# Serial_IO.net
KiCad netlist of a schematic drawn in Altium Designer
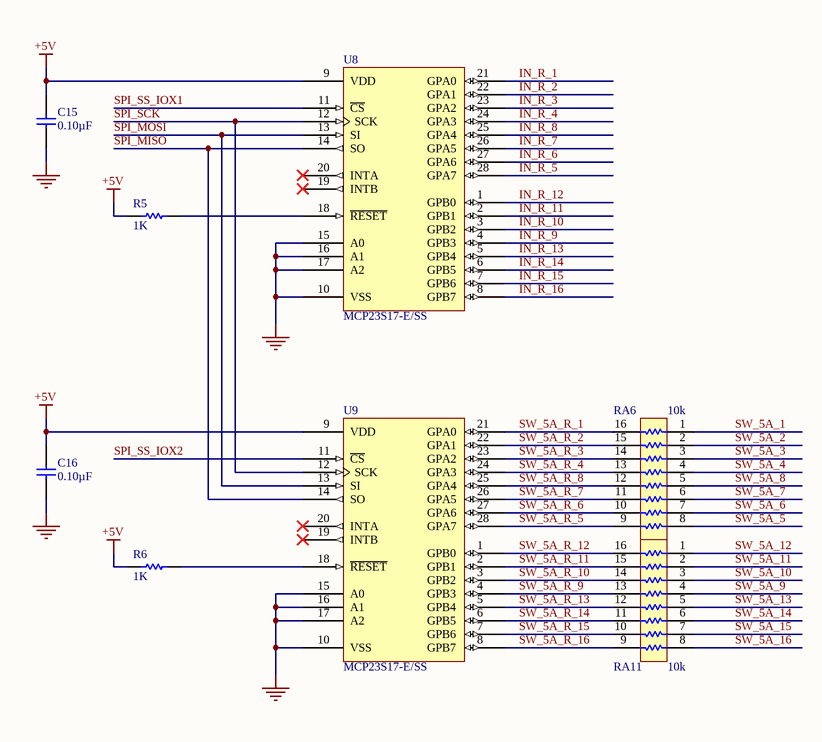
[diagram p0: Serial IO.SchDoc]

(export (version "E")
  (design (tool "Eeschema 10.0.6"))
  (components
    (comp (ref "C15")
      (value "0.10µF")
      (footprint "CAP-0402-M")
      (fields
        (field (name "PART NUMBER") "CC0402KRX7R7BB104")
        (field (name "TOLERANCE") "±10%")
        (field (name "VOLTAGE") "16V")
      )
      (libsource (lib "Capacitors") (part "Capacitor"))
    )
    (comp (ref "C16")
      (value "0.10µF")
      (footprint "CAP-0402-M")
      (fields
        (field (name "PART NUMBER") "CC0402KRX7R7BB104")
        (field (name "TOLERANCE") "±10%")
        (field (name "VOLTAGE") "16V")
      )
      (libsource (lib "Capacitors") (part "Capacitor"))
    )
    (comp (ref "R5")
      (value "1K")
      (footprint "RES-0603-M")
      (fields
        (field (name "PART NUMBER") "RC0603FR-071KL")
        (field (name "TOLERANCE") "1%")
        (field (name "POWER") "1/10 W")
      )
      (libsource (lib "Resistors") (part "Resistor"))
    )
    (comp (ref "R6")
      (value "1K")
      (footprint "RES-0603-M")
      (fields
        (field (name "PART NUMBER") "RC0603FR-071KL")
        (field (name "TOLERANCE") "1%")
        (field (name "POWER") "1/10 W")
      )
      (libsource (lib "Resistors") (part "Resistor"))
    )
    (comp (ref "RA6")
      (value "10k")
      (footprint "CAC-50P379X150-16N")
      (fields (field (name "Comment") "MNR18ERAPJ103"))
      (libsource (lib "PDU-UV17") (part "MNR18ERAPJ103"))
    )
    (comp (ref "RA11")
      (value "10k")
      (footprint "CAC-50P379X150-16N")
      (fields (field (name "Comment") "MNR18ERAPJ103"))
      (libsource (lib "PDU-UV17") (part "MNR18ERAPJ103"))
    )
    (comp (ref "U8")
      (value "MCP23S17-E/SS")
      (footprint "SOP65P780X185-28N")
      (libsource (lib "PDU-UV17") (part "MCP23S17-E/SS"))
    )
    (comp (ref "U9")
      (value "MCP23S17-E/SS")
      (footprint "SOP65P780X185-28N")
      (libsource (lib "PDU-UV17") (part "MCP23S17-E/SS"))
    )
  )
  (nets
    (net (code "1") (name "+5V") (class "Default")
      (node (ref "C15") (pin "2") (pinfunction "2_2") (pintype "passive"))
      (node (ref "C16") (pin "2") (pinfunction "2_2") (pintype "passive"))
      (node (ref "R5") (pin "1") (pinfunction "1_1") (pintype "passive"))
      (node (ref "R6") (pin "1") (pinfunction "1_1") (pintype "passive"))
      (node (ref "U8") (pin "9") (pinfunction "VDD_9") (pintype "power_in"))
      (node (ref "U9") (pin "9") (pinfunction "VDD_9") (pintype "power_in"))
    )
    (net (code "2") (name "/IN_R_1") (class "Default")
      (node (ref "U8") (pin "21") (pinfunction "GPA0_21") (pintype "bidirectional"))
    )
    (net (code "3") (name "/IN_R_2") (class "Default")
      (node (ref "U8") (pin "22") (pinfunction "GPA1_22") (pintype "bidirectional"))
    )
    (net (code "4") (name "/IN_R_3") (class "Default")
      (node (ref "U8") (pin "23") (pinfunction "GPA2_23") (pintype "bidirectional"))
    )
    (net (code "5") (name "/IN_R_4") (class "Default")
      (node (ref "U8") (pin "24") (pinfunction "GPA3_24") (pintype "bidirectional"))
    )
    (net (code "6") (name "/IN_R_5") (class "Default")
      (node (ref "U8") (pin "28") (pinfunction "GPA7_28") (pintype "bidirectional"))
    )
    (net (code "7") (name "/IN_R_6") (class "Default")
      (node (ref "U8") (pin "27") (pinfunction "GPA6_27") (pintype "bidirectional"))
    )
    (net (code "8") (name "/IN_R_7") (class "Default")
      (node (ref "U8") (pin "26") (pinfunction "GPA5_26") (pintype "bidirectional"))
    )
    (net (code "9") (name "/IN_R_8") (class "Default")
      (node (ref "U8") (pin "25") (pinfunction "GPA4_25") (pintype "bidirectional"))
    )
    (net (code "10") (name "/IN_R_9") (class "Default")
      (node (ref "U8") (pin "4") (pinfunction "GPB3_4") (pintype "bidirectional"))
    )
    (net (code "11") (name "/IN_R_10") (class "Default")
      (node (ref "U8") (pin "3") (pinfunction "GPB2_3") (pintype "bidirectional"))
    )
    (net (code "12") (name "/IN_R_11") (class "Default")
      (node (ref "U8") (pin "2") (pinfunction "GPB1_2") (pintype "bidirectional"))
    )
    (net (code "13") (name "/IN_R_12") (class "Default")
      (node (ref "U8") (pin "1") (pinfunction "GPB0_1") (pintype "bidirectional"))
    )
    (net (code "14") (name "/IN_R_13") (class "Default")
      (node (ref "U8") (pin "5") (pinfunction "GPB4_5") (pintype "bidirectional"))
    )
    (net (code "15") (name "/IN_R_14") (class "Default")
      (node (ref "U8") (pin "6") (pinfunction "GPB5_6") (pintype "bidirectional"))
    )
    (net (code "16") (name "/IN_R_15") (class "Default")
      (node (ref "U8") (pin "7") (pinfunction "GPB6_7") (pintype "bidirectional"))
    )
    (net (code "17") (name "/IN_R_16") (class "Default")
      (node (ref "U8") (pin "8") (pinfunction "GPB7_8") (pintype "bidirectional"))
    )
    (net (code "18") (name "/SPI_MISO") (class "Default")
      (node (ref "U8") (pin "14") (pinfunction "SO_14") (pintype "output"))
      (node (ref "U9") (pin "14") (pinfunction "SO_14") (pintype "output"))
    )
    (net (code "19") (name "/SPI_MOSI") (class "Default")
      (node (ref "U8") (pin "13") (pinfunction "SI_13") (pintype "input"))
      (node (ref "U9") (pin "13") (pinfunction "SI_13") (pintype "input"))
    )
    (net (code "20") (name "/SPI_SCK") (class "Default")
      (node (ref "U8") (pin "12") (pinfunction "SCK_12") (pintype "input"))
      (node (ref "U9") (pin "12") (pinfunction "SCK_12") (pintype "input"))
    )
    (net (code "21") (name "/SPI_SS_IOX1") (class "Default")
      (node (ref "U8") (pin "11") (pinfunction "~{CS}_11") (pintype "input"))
    )
    (net (code "22") (name "/SPI_SS_IOX2") (class "Default")
      (node (ref "U9") (pin "11") (pinfunction "~{CS}_11") (pintype "input"))
    )
    (net (code "23") (name "/SW_5A_1") (class "Default")
      (node (ref "RA6") (pin "1") (pinfunction "1_1") (pintype "passive"))
    )
    (net (code "24") (name "/SW_5A_2") (class "Default")
      (node (ref "RA6") (pin "2") (pinfunction "2_2") (pintype "passive"))
    )
    (net (code "25") (name "/SW_5A_3") (class "Default")
      (node (ref "RA6") (pin "3") (pinfunction "3_3") (pintype "passive"))
    )
    (net (code "26") (name "/SW_5A_4") (class "Default")
      (node (ref "RA6") (pin "4") (pinfunction "4_4") (pintype "passive"))
    )
    (net (code "27") (name "/SW_5A_5") (class "Default")
      (node (ref "RA6") (pin "8") (pinfunction "8_8") (pintype "passive"))
    )
    (net (code "28") (name "/SW_5A_6") (class "Default")
      (node (ref "RA6") (pin "7") (pinfunction "7_7") (pintype "passive"))
    )
    (net (code "29") (name "/SW_5A_7") (class "Default")
      (node (ref "RA6") (pin "6") (pinfunction "6_6") (pintype "passive"))
    )
    (net (code "30") (name "/SW_5A_8") (class "Default")
      (node (ref "RA6") (pin "5") (pinfunction "5_5") (pintype "passive"))
    )
    (net (code "31") (name "/SW_5A_9") (class "Default")
      (node (ref "RA11") (pin "4") (pinfunction "4_4") (pintype "passive"))
    )
    (net (code "32") (name "/SW_5A_10") (class "Default")
      (node (ref "RA11") (pin "3") (pinfunction "3_3") (pintype "passive"))
    )
    (net (code "33") (name "/SW_5A_11") (class "Default")
      (node (ref "RA11") (pin "2") (pinfunction "2_2") (pintype "passive"))
    )
    (net (code "34") (name "/SW_5A_12") (class "Default")
      (node (ref "RA11") (pin "1") (pinfunction "1_1") (pintype "passive"))
    )
    (net (code "35") (name "/SW_5A_13") (class "Default")
      (node (ref "RA11") (pin "5") (pinfunction "5_5") (pintype "passive"))
    )
    (net (code "36") (name "/SW_5A_14") (class "Default")
      (node (ref "RA11") (pin "6") (pinfunction "6_6") (pintype "passive"))
    )
    (net (code "37") (name "/SW_5A_15") (class "Default")
      (node (ref "RA11") (pin "7") (pinfunction "7_7") (pintype "passive"))
    )
    (net (code "38") (name "/SW_5A_16") (class "Default")
      (node (ref "RA11") (pin "8") (pinfunction "8_8") (pintype "passive"))
    )
    (net (code "39") (name "/SW_5A_R_1") (class "Default")
      (node (ref "RA6") (pin "16") (pinfunction "16_16") (pintype "passive"))
      (node (ref "U9") (pin "21") (pinfunction "GPA0_21") (pintype "bidirectional"))
    )
    (net (code "40") (name "/SW_5A_R_2") (class "Default")
      (node (ref "RA6") (pin "15") (pinfunction "15_15") (pintype "passive"))
      (node (ref "U9") (pin "22") (pinfunction "GPA1_22") (pintype "bidirectional"))
    )
    (net (code "41") (name "/SW_5A_R_3") (class "Default")
      (node (ref "RA6") (pin "14") (pinfunction "14_14") (pintype "passive"))
      (node (ref "U9") (pin "23") (pinfunction "GPA2_23") (pintype "bidirectional"))
    )
    (net (code "42") (name "/SW_5A_R_4") (class "Default")
      (node (ref "RA6") (pin "13") (pinfunction "13_13") (pintype "passive"))
      (node (ref "U9") (pin "24") (pinfunction "GPA3_24") (pintype "bidirectional"))
    )
    (net (code "43") (name "/SW_5A_R_5") (class "Default")
      (node (ref "RA6") (pin "9") (pinfunction "9_9") (pintype "passive"))
      (node (ref "U9") (pin "28") (pinfunction "GPA7_28") (pintype "bidirectional"))
    )
    (net (code "44") (name "/SW_5A_R_6") (class "Default")
      (node (ref "RA6") (pin "10") (pinfunction "10_10") (pintype "passive"))
      (node (ref "U9") (pin "27") (pinfunction "GPA6_27") (pintype "bidirectional"))
    )
    (net (code "45") (name "/SW_5A_R_7") (class "Default")
      (node (ref "RA6") (pin "11") (pinfunction "11_11") (pintype "passive"))
      (node (ref "U9") (pin "26") (pinfunction "GPA5_26") (pintype "bidirectional"))
    )
    (net (code "46") (name "/SW_5A_R_8") (class "Default")
      (node (ref "RA6") (pin "12") (pinfunction "12_12") (pintype "passive"))
      (node (ref "U9") (pin "25") (pinfunction "GPA4_25") (pintype "bidirectional"))
    )
    (net (code "47") (name "/SW_5A_R_9") (class "Default")
      (node (ref "RA11") (pin "13") (pinfunction "13_13") (pintype "passive"))
      (node (ref "U9") (pin "4") (pinfunction "GPB3_4") (pintype "bidirectional"))
    )
    (net (code "48") (name "/SW_5A_R_10") (class "Default")
      (node (ref "RA11") (pin "14") (pinfunction "14_14") (pintype "passive"))
      (node (ref "U9") (pin "3") (pinfunction "GPB2_3") (pintype "bidirectional"))
    )
    (net (code "49") (name "/SW_5A_R_11") (class "Default")
      (node (ref "RA11") (pin "15") (pinfunction "15_15") (pintype "passive"))
      (node (ref "U9") (pin "2") (pinfunction "GPB1_2") (pintype "bidirectional"))
    )
    (net (code "50") (name "/SW_5A_R_12") (class "Default")
      (node (ref "RA11") (pin "16") (pinfunction "16_16") (pintype "passive"))
      (node (ref "U9") (pin "1") (pinfunction "GPB0_1") (pintype "bidirectional"))
    )
    (net (code "51") (name "/SW_5A_R_13") (class "Default")
      (node (ref "RA11") (pin "12") (pinfunction "12_12") (pintype "passive"))
      (node (ref "U9") (pin "5") (pinfunction "GPB4_5") (pintype "bidirectional"))
    )
    (net (code "52") (name "/SW_5A_R_14") (class "Default")
      (node (ref "RA11") (pin "11") (pinfunction "11_11") (pintype "passive"))
      (node (ref "U9") (pin "6") (pinfunction "GPB5_6") (pintype "bidirectional"))
    )
    (net (code "53") (name "/SW_5A_R_15") (class "Default")
      (node (ref "RA11") (pin "10") (pinfunction "10_10") (pintype "passive"))
      (node (ref "U9") (pin "7") (pinfunction "GPB6_7") (pintype "bidirectional"))
    )
    (net (code "54") (name "/SW_5A_R_16") (class "Default")
      (node (ref "RA11") (pin "9") (pinfunction "9_9") (pintype "passive"))
      (node (ref "U9") (pin "8") (pinfunction "GPB7_8") (pintype "bidirectional"))
    )
    (net (code "55") (name "GND") (class "Default")
      (node (ref "C15") (pin "1") (pinfunction "1_1") (pintype "passive"))
      (node (ref "C16") (pin "1") (pinfunction "1_1") (pintype "passive"))
      (node (ref "U8") (pin "10") (pinfunction "VSS_10") (pintype "power_in"))
      (node (ref "U8") (pin "15") (pinfunction "A0_15") (pintype "passive"))
      (node (ref "U8") (pin "16") (pinfunction "A1_16") (pintype "passive"))
      (node (ref "U8") (pin "17") (pinfunction "A2_17") (pintype "passive"))
      (node (ref "U9") (pin "10") (pinfunction "VSS_10") (pintype "power_in"))
      (node (ref "U9") (pin "15") (pinfunction "A0_15") (pintype "passive"))
      (node (ref "U9") (pin "16") (pinfunction "A1_16") (pintype "passive"))
      (node (ref "U9") (pin "17") (pinfunction "A2_17") (pintype "passive"))
    )
    (net (code "56") (name "Net-(U8-~{RESET})") (class "Default")
      (node (ref "R5") (pin "2") (pinfunction "2_2") (pintype "passive"))
      (node (ref "U8") (pin "18") (pinfunction "~{RESET}_18") (pintype "input"))
    )
    (net (code "57") (name "Net-(U9-~{RESET})") (class "Default")
      (node (ref "R6") (pin "2") (pinfunction "2_2") (pintype "passive"))
      (node (ref "U9") (pin "18") (pinfunction "~{RESET}_18") (pintype "input"))
    )
    (net (code "58") (name "unconnected-(U8-INTA-Pad20)") (class "Default")
      (node (ref "U8") (pin "20") (pinfunction "INTA_20") (pintype "output+no_connect"))
    )
    (net (code "59") (name "unconnected-(U8-INTB-Pad19)") (class "Default")
      (node (ref "U8") (pin "19") (pinfunction "INTB_19") (pintype "output+no_connect"))
    )
    (net (code "60") (name "unconnected-(U9-INTA-Pad20)") (class "Default")
      (node (ref "U9") (pin "20") (pinfunction "INTA_20") (pintype "output+no_connect"))
    )
    (net (code "61") (name "unconnected-(U9-INTB-Pad19)") (class "Default")
      (node (ref "U9") (pin "19") (pinfunction "INTB_19") (pintype "output+no_connect"))
    )
  )
)
